# 24_063.net
KiCad netlist of a schematic drawn in Altium Designer
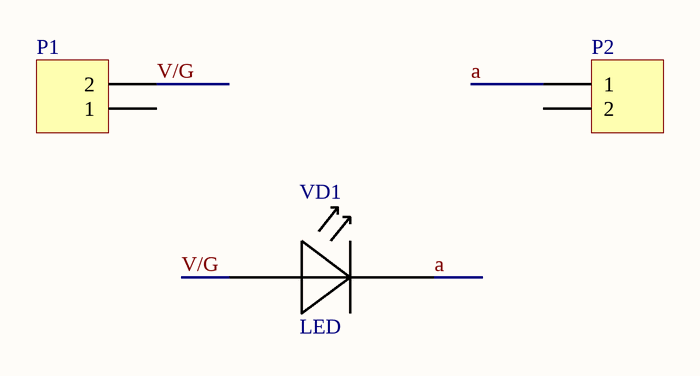
[diagram p0: 24.063.SchDoc]

(export (version "E")
  (design (tool "Eeschema 10.0.6"))
  (components
    (comp (ref "P1")
      (value "Header 2")
      (footprint "HDR1X2")
      (description "Header, 2-Pin")
      (fields (field (name "PUBLISHER") "Altium Limited"))
      (libsource (lib "Miscellaneous Connectors") (part "Header 2"))
    )
    (comp (ref "P2")
      (value "Header 2")
      (footprint "HDR1X2")
      (description "Header, 2-Pin")
      (fields (field (name "PUBLISHER") "Altium Limited"))
      (libsource (lib "") (part "Header 2_1"))
    )
    (comp (ref "VD1") (value "LED") (footprint "LED 24.063") (libsource (lib "msp_SchLib") (part "LED")))
  )
  (nets
    (net (code "1") (name "/V{slash}G") (class "Default")
      (node (ref "P1") (pin "2") (pinfunction "2_2") (pintype "passive"))
      (node (ref "VD1") (pin "1") (pinfunction "1_1") (pintype "passive"))
    )
    (net (code "2") (name "/a") (class "Default")
      (node (ref "P2") (pin "1") (pinfunction "1_1") (pintype "passive"))
      (node (ref "VD1") (pin "2") (pinfunction "2_2") (pintype "passive"))
    )
    (net (code "3") (name "unconnected-(P1-Pad1)") (class "Default")
      (node (ref "P1") (pin "1") (pinfunction "1_1") (pintype "passive"))
    )
    (net (code "4") (name "unconnected-(P2-Pad2)") (class "Default")
      (node (ref "P2") (pin "2") (pinfunction "2_2") (pintype "passive"))
    )
  )
)
